# APDS-9801.net
KiCad netlist of a schematic drawn in EAGLE
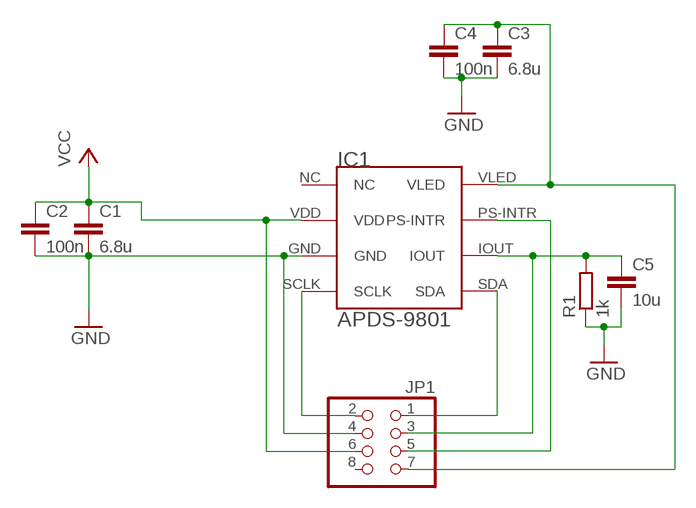
[diagram p0: schematic, sheet 1]

(export (version "E")
  (design (tool "Eeschema 10.0.6"))
  (components
    (comp (ref "C1")
      (value "6.8u")
      (footprint "eagle-import:C0805")
      (libsource (lib "eagle-import") (part "C-EUC0805"))
    )
    (comp (ref "C2")
      (value "100n")
      (footprint "eagle-import:C0805")
      (libsource (lib "eagle-import") (part "C-EUC0805"))
    )
    (comp (ref "C3")
      (value "6.8u")
      (footprint "eagle-import:C0805")
      (libsource (lib "eagle-import") (part "C-EUC0805"))
    )
    (comp (ref "C4")
      (value "100n")
      (footprint "eagle-import:C0805")
      (libsource (lib "eagle-import") (part "C-EUC0805"))
    )
    (comp (ref "C5")
      (value "10u")
      (footprint "eagle-import:C0805")
      (libsource (lib "eagle-import") (part "C-EUC0805"))
    )
    (comp (ref "IC1")
      (value "APDS-9801")
      (footprint "eagle-import:APDS-9801")
      (libsource (lib "eagle-import") (part "APDS-9801"))
    )
    (comp (ref "JP1")
      (value "PINHD-2X4")
      (footprint "eagle-import:2X04")
      (libsource (lib "eagle-import") (part "PINHD-2X4"))
    )
    (comp (ref "R1")
      (value "1k")
      (footprint "eagle-import:M0805")
      (libsource (lib "eagle-import") (part "R-EU_M0805"))
    )
  )
  (nets
    (net (code "1") (name "GND") (class "Default")
      (node (ref "C1") (pin "2") (pinfunction "2_2") (pintype "passive"))
      (node (ref "C2") (pin "2") (pinfunction "2_2") (pintype "passive"))
      (node (ref "C3") (pin "2") (pinfunction "2_2") (pintype "passive"))
      (node (ref "C4") (pin "2") (pinfunction "2_2") (pintype "passive"))
      (node (ref "C5") (pin "2") (pinfunction "2_2") (pintype "passive"))
      (node (ref "IC1") (pin "GND") (pinfunction "GND_GND") (pintype "power_in"))
      (node (ref "JP1") (pin "4") (pinfunction "4_4") (pintype "passive"))
      (node (ref "R1") (pin "1") (pinfunction "1_1") (pintype "passive"))
    )
    (net (code "2") (name "Net-(C3-Pad1)") (class "Default")
      (node (ref "C3") (pin "1") (pinfunction "1_1") (pintype "passive"))
      (node (ref "C4") (pin "1") (pinfunction "1_1") (pintype "passive"))
      (node (ref "IC1") (pin "VLED") (pinfunction "VLED_VLED") (pintype "power_in"))
      (node (ref "JP1") (pin "7") (pinfunction "7_7") (pintype "passive"))
    )
    (net (code "3") (name "Net-(C5-Pad1)") (class "Default")
      (node (ref "C5") (pin "1") (pinfunction "1_1") (pintype "passive"))
      (node (ref "IC1") (pin "IOUT") (pinfunction "IOUT_IOUT") (pintype "input"))
      (node (ref "JP1") (pin "3") (pinfunction "3_3") (pintype "passive"))
      (node (ref "R1") (pin "2") (pinfunction "2_2") (pintype "passive"))
    )
    (net (code "4") (name "Net-(IC1-PadPS-INTR)") (class "Default")
      (node (ref "IC1") (pin "PS-INTR") (pinfunction "PS-INTR_PS-INTR") (pintype "output"))
      (node (ref "JP1") (pin "5") (pinfunction "5_5") (pintype "passive"))
    )
    (net (code "5") (name "Net-(IC1-PadSCLK)") (class "Default")
      (node (ref "IC1") (pin "SCLK") (pinfunction "SCLK_SCLK") (pintype "bidirectional"))
      (node (ref "JP1") (pin "2") (pinfunction "2_2") (pintype "passive"))
    )
    (net (code "6") (name "Net-(IC1-PadSDA)") (class "Default")
      (node (ref "IC1") (pin "SDA") (pinfunction "SDA_SDA") (pintype "bidirectional"))
      (node (ref "JP1") (pin "1") (pinfunction "1_1") (pintype "passive"))
    )
    (net (code "7") (name "VCC") (class "Default")
      (node (ref "C1") (pin "1") (pinfunction "1_1") (pintype "passive"))
      (node (ref "C2") (pin "1") (pinfunction "1_1") (pintype "passive"))
      (node (ref "IC1") (pin "VDD") (pinfunction "VDD_VDD") (pintype "power_in"))
      (node (ref "JP1") (pin "6") (pinfunction "6_6") (pintype "passive"))
    )
    (net (code "8") (name "unconnected-(IC1-PadNC)") (class "Default")
      (node (ref "IC1") (pin "NC") (pinfunction "NC_NC") (pintype "no_connect"))
    )
    (net (code "9") (name "unconnected-(JP1-Pad8)") (class "Default")
      (node (ref "JP1") (pin "8") (pinfunction "8_8") (pintype "passive"))
    )
  )
)
